# PCB-TLY-SHLD.net
KiCad netlist of a schematic drawn in EAGLE
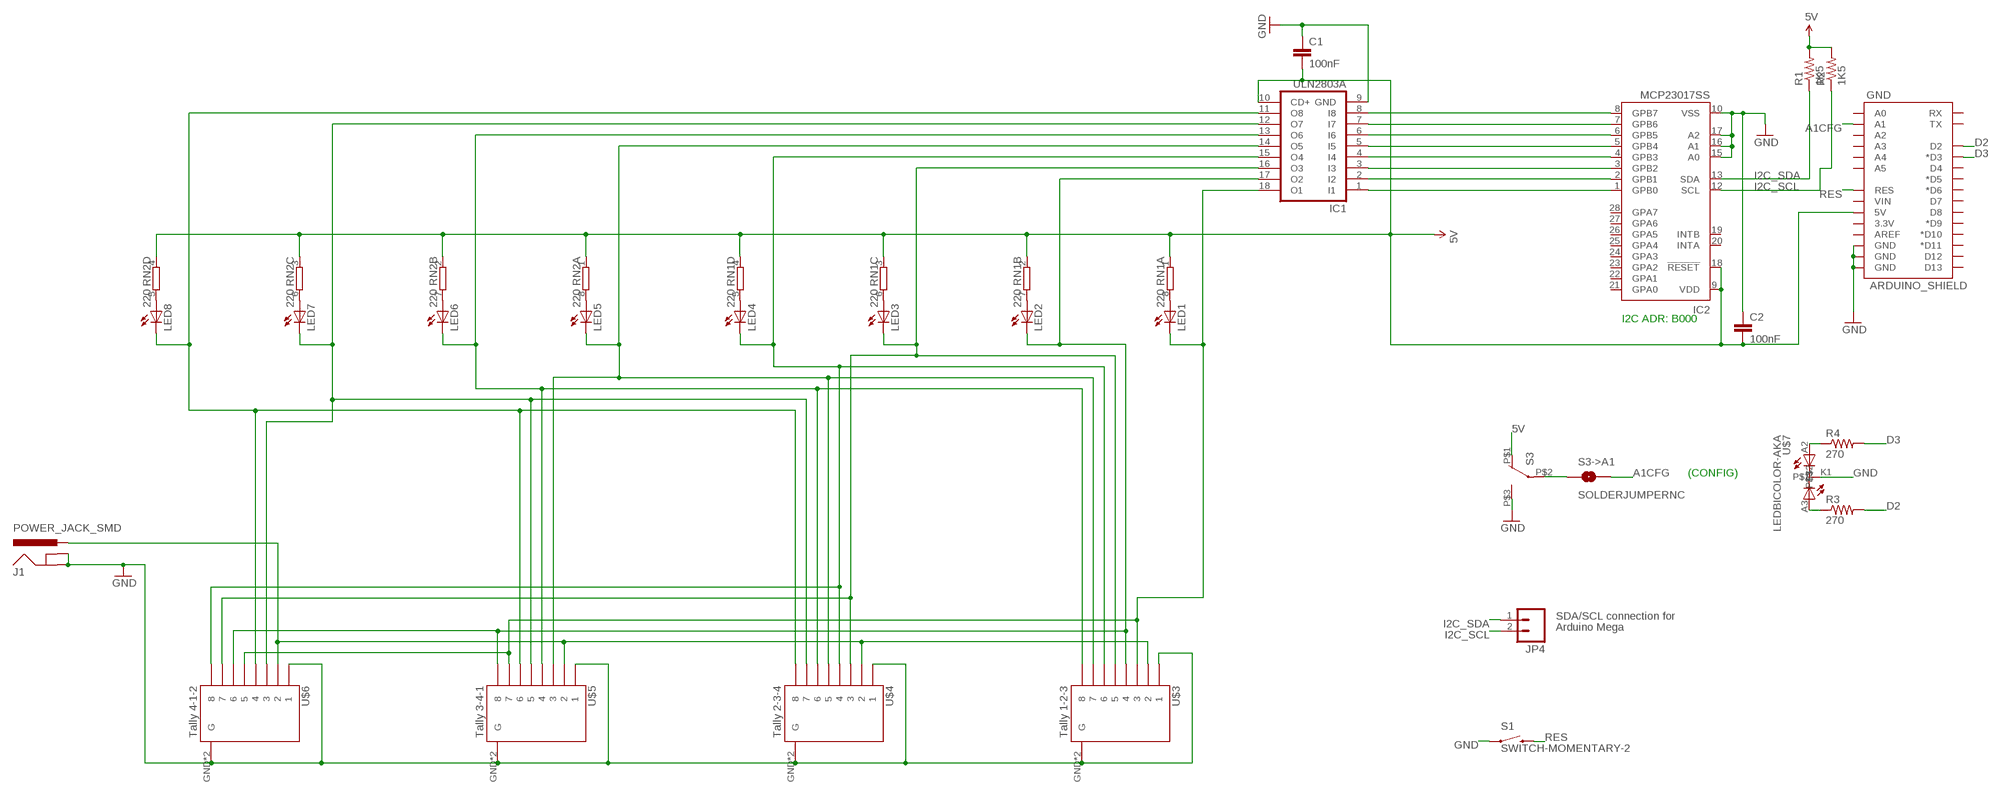
[diagram p0: schematic, sheet 1]

(export (version "E")
  (design (tool "Eeschema 10.0.6"))
  (components
    (comp (ref "C1")
      (value "100nF")
      (footprint "eagle-import:0805")
      (libsource (lib "eagle-import") (part "CAP0805"))
    )
    (comp (ref "C2")
      (value "100nF")
      (footprint "eagle-import:0603-CAP")
      (libsource (lib "eagle-import") (part "CAP0603-CAP"))
    )
    (comp (ref "GND")
      (value "ARDUINO_SHIELD")
      (footprint "eagle-import:ARDUINO_BOXSHIELD_NOHOLES")
      (libsource (lib "eagle-import") (part "ARDUINO_SHIELD"))
    )
    (comp (ref "IC1")
      (value "ULN2803A")
      (footprint "eagle-import:SO18W")
      (libsource (lib "eagle-import") (part "ULN2803ASO18W"))
    )
    (comp (ref "IC2")
      (value "MCP23017SS")
      (footprint "eagle-import:SSOP28")
      (fields (field (name "MF") "MICROCHIP") (field (name "MPN") "MCP23017-E/SS"))
      (libsource (lib "eagle-import") (part "MCP23017SS"))
    )
    (comp (ref "J1")
      (value "POWER_JACK_SMD")
      (footprint "eagle-import:POWER_JACK_SMD")
      (libsource (lib "eagle-import") (part "POWER_JACK_SMD"))
    )
    (comp (ref "JP4")
      (value "M02PTH")
      (footprint "eagle-import:1X02")
      (libsource (lib "eagle-import") (part "M02PTH"))
    )
    (comp (ref "LED1")
      (value "LEDSML0805")
      (footprint "eagle-import:SML0805")
      (libsource (lib "eagle-import") (part "LEDSML0805"))
    )
    (comp (ref "LED2")
      (value "LEDSML0805")
      (footprint "eagle-import:SML0805")
      (libsource (lib "eagle-import") (part "LEDSML0805"))
    )
    (comp (ref "LED3")
      (value "LEDSML0805")
      (footprint "eagle-import:SML0805")
      (libsource (lib "eagle-import") (part "LEDSML0805"))
    )
    (comp (ref "LED4")
      (value "LEDSML0805")
      (footprint "eagle-import:SML0805")
      (libsource (lib "eagle-import") (part "LEDSML0805"))
    )
    (comp (ref "LED5")
      (value "LEDSML0805")
      (footprint "eagle-import:SML0805")
      (libsource (lib "eagle-import") (part "LEDSML0805"))
    )
    (comp (ref "LED6")
      (value "LEDSML0805")
      (footprint "eagle-import:SML0805")
      (libsource (lib "eagle-import") (part "LEDSML0805"))
    )
    (comp (ref "LED7")
      (value "LEDSML0805")
      (footprint "eagle-import:SML0805")
      (libsource (lib "eagle-import") (part "LEDSML0805"))
    )
    (comp (ref "LED8")
      (value "LEDSML0805")
      (footprint "eagle-import:SML0805")
      (libsource (lib "eagle-import") (part "LEDSML0805"))
    )
    (comp (ref "R1")
      (value "1K5")
      (footprint "eagle-import:0603-RES")
      (libsource (lib "eagle-import") (part "RESISTOR0603-RES"))
    )
    (comp (ref "R2")
      (value "1K5")
      (footprint "eagle-import:0603-RES")
      (libsource (lib "eagle-import") (part "RESISTOR0603-RES"))
    )
    (comp (ref "R3")
      (value "270")
      (footprint "eagle-import:0603-RES")
      (libsource (lib "eagle-import") (part "RESISTOR0603-RES"))
    )
    (comp (ref "R4")
      (value "270")
      (footprint "eagle-import:0603-RES")
      (libsource (lib "eagle-import") (part "RESISTOR0603-RES"))
    )
    (comp (ref "RN1")
      (value "220")
      (footprint "eagle-import:CAY16_HAND")
      (libsource (lib "eagle-import") (part "4R-NCAY16"))
    )
    (comp (ref "RN2")
      (value "220")
      (footprint "eagle-import:CAY16_HAND")
      (libsource (lib "eagle-import") (part "4R-NCAY16"))
    )
    (comp (ref "S1")
      (value "SWITCH-MOMENTARY-2")
      (footprint "eagle-import:TACTILE_SWITCH_TALL")
      (libsource (lib "eagle-import") (part "SWITCH-MOMENTARY-2"))
    )
    (comp (ref "S3")
      (value "CFG")
      (footprint "eagle-import:TECONNECTIVITY-DPST")
      (libsource (lib "eagle-import") (part "SWITCH-DPST"))
    )
    (comp (ref "S3->A1")
      (value "SOLDERJUMPERNC")
      (footprint "eagle-import:SJ_2S")
      (libsource (lib "eagle-import") (part "SOLDERJUMPERNC"))
    )
    (comp (ref "U$3")
      (value "Tally 1-2-3")
      (footprint "eagle-import:RJ45-8_GND")
      (libsource (lib "eagle-import") (part "RJ45-8_GND"))
    )
    (comp (ref "U$4")
      (value "Tally 2-3-4")
      (footprint "eagle-import:RJ45-8_GND")
      (libsource (lib "eagle-import") (part "RJ45-8_GND"))
    )
    (comp (ref "U$5")
      (value "Tally 3-4-1")
      (footprint "eagle-import:RJ45-8_GND")
      (libsource (lib "eagle-import") (part "RJ45-8_GND"))
    )
    (comp (ref "U$6")
      (value "Tally 4-1-2")
      (footprint "eagle-import:RJ45-8_GND")
      (libsource (lib "eagle-import") (part "RJ45-8_GND"))
    )
    (comp (ref "U$7")
      (value "LEDBICOLOR-AKA")
      (footprint "eagle-import:LED5MM-BICOLOR")
      (libsource (lib "eagle-import") (part "LEDBICOLOR-AKA"))
    )
  )
  (nets
    (net (code "1") (name "/A1CFG") (class "Default")
      (node (ref "GND") (pin "A1") (pinfunction "A1_A1") (pintype "bidirectional"))
      (node (ref "S3->A1") (pin "2") (pinfunction "2_2") (pintype "passive"))
    )
    (net (code "2") (name "/D2") (class "Default")
      (node (ref "GND") (pin "2") (pinfunction "D2_2") (pintype "bidirectional"))
      (node (ref "R3") (pin "2") (pinfunction "2_2") (pintype "passive"))
    )
    (net (code "3") (name "/D3") (class "Default")
      (node (ref "GND") (pin "3") (pinfunction "*D3_3") (pintype "bidirectional"))
      (node (ref "R4") (pin "2") (pinfunction "2_2") (pintype "passive"))
    )
    (net (code "4") (name "/I2C_SCL") (class "Default")
      (node (ref "IC2") (pin "12") (pinfunction "SCL_12") (pintype "input"))
      (node (ref "JP4") (pin "2") (pinfunction "2_2") (pintype "passive"))
      (node (ref "R2") (pin "1") (pinfunction "1_1") (pintype "passive"))
    )
    (net (code "5") (name "/I2C_SDA") (class "Default")
      (node (ref "IC2") (pin "13") (pinfunction "SDA_13") (pintype "bidirectional"))
      (node (ref "JP4") (pin "1") (pinfunction "1_1") (pintype "passive"))
      (node (ref "R1") (pin "1") (pinfunction "1_1") (pintype "passive"))
    )
    (net (code "6") (name "/RES") (class "Default")
      (node (ref "GND") (pin "RESET") (pinfunction "RES_RESET") (pintype "bidirectional"))
      (node (ref "S1") (pin "B2") (pinfunction "2_B2") (pintype "passive"))
    )
    (net (code "7") (name "5V") (class "Default")
      (node (ref "C1") (pin "2") (pinfunction "2_2") (pintype "passive"))
      (node (ref "C2") (pin "2") (pinfunction "2_2") (pintype "passive"))
      (node (ref "GND") (pin "5V@0") (pinfunction "5V_5V@0") (pintype "bidirectional"))
      (node (ref "IC1") (pin "10") (pinfunction "CD+_10") (pintype "passive"))
      (node (ref "IC2") (pin "18") (pinfunction "~{RESET}_18") (pintype "input"))
      (node (ref "IC2") (pin "9") (pinfunction "VDD_9") (pintype "power_in"))
      (node (ref "R1") (pin "2") (pinfunction "2_2") (pintype "passive"))
      (node (ref "R2") (pin "2") (pinfunction "2_2") (pintype "passive"))
      (node (ref "RN1") (pin "1") (pinfunction "1_1") (pintype "passive"))
      (node (ref "RN1") (pin "2") (pinfunction "1_2") (pintype "passive"))
      (node (ref "RN1") (pin "3") (pinfunction "1_3") (pintype "passive"))
      (node (ref "RN1") (pin "4") (pinfunction "1_4") (pintype "passive"))
      (node (ref "RN2") (pin "1") (pinfunction "1_1") (pintype "passive"))
      (node (ref "RN2") (pin "2") (pinfunction "1_2") (pintype "passive"))
      (node (ref "RN2") (pin "3") (pinfunction "1_3") (pintype "passive"))
      (node (ref "RN2") (pin "4") (pinfunction "1_4") (pintype "passive"))
      (node (ref "S3") (pin "P$1") (pinfunction "O_P$1") (pintype "passive"))
    )
    (net (code "8") (name "GND") (class "Default")
      (node (ref "C1") (pin "1") (pinfunction "1_1") (pintype "passive"))
      (node (ref "C2") (pin "1") (pinfunction "1_1") (pintype "passive"))
      (node (ref "GND") (pin "GND@0") (pinfunction "GND_GND@0") (pintype "bidirectional"))
      (node (ref "GND") (pin "GND@1") (pinfunction "GND_GND@1") (pintype "bidirectional"))
      (node (ref "GND") (pin "GND@4") (pinfunction "GND_GND@4") (pintype "bidirectional"))
      (node (ref "IC1") (pin "9") (pinfunction "GND_9") (pintype "power_in"))
      (node (ref "IC2") (pin "10") (pinfunction "VSS_10") (pintype "power_in"))
      (node (ref "IC2") (pin "15") (pinfunction "A0_15") (pintype "input"))
      (node (ref "IC2") (pin "16") (pinfunction "A1_16") (pintype "input"))
      (node (ref "IC2") (pin "17") (pinfunction "A2_17") (pintype "input"))
      (node (ref "J1") (pin "GND") (pinfunction "GND_GND") (pintype "bidirectional"))
      (node (ref "J1") (pin "SHUNT") (pinfunction "GNDBREAK_SHUNT") (pintype "bidirectional"))
      (node (ref "S1") (pin "A2") (pinfunction "1_A2") (pintype "passive"))
      (node (ref "S3") (pin "P$3") (pinfunction "S_P$3") (pintype "passive"))
      (node (ref "U$3") (pin "1") (pinfunction "1_1") (pintype "bidirectional"))
      (node (ref "U$3") (pin "GND") (pinfunction "G_GND") (pintype "power_in"))
      (node (ref "U$3") (pin "GND1") (pinfunction "G_GND1") (pintype "power_in"))
      (node (ref "U$4") (pin "1") (pinfunction "1_1") (pintype "bidirectional"))
      (node (ref "U$4") (pin "GND") (pinfunction "G_GND") (pintype "power_in"))
      (node (ref "U$4") (pin "GND1") (pinfunction "G_GND1") (pintype "power_in"))
      (node (ref "U$5") (pin "1") (pinfunction "1_1") (pintype "bidirectional"))
      (node (ref "U$5") (pin "GND") (pinfunction "G_GND") (pintype "power_in"))
      (node (ref "U$5") (pin "GND1") (pinfunction "G_GND1") (pintype "power_in"))
      (node (ref "U$6") (pin "1") (pinfunction "1_1") (pintype "bidirectional"))
      (node (ref "U$6") (pin "GND") (pinfunction "G_GND") (pintype "power_in"))
      (node (ref "U$6") (pin "GND1") (pinfunction "G_GND1") (pintype "power_in"))
      (node (ref "U$7") (pin "K1") (pinfunction "P$1_K1") (pintype "bidirectional"))
    )
    (net (code "9") (name "Net-(IC1-I1)") (class "Default")
      (node (ref "IC1") (pin "1") (pinfunction "I1_1") (pintype "input"))
      (node (ref "IC2") (pin "1") (pinfunction "GPB0_1") (pintype "bidirectional"))
    )
    (net (code "10") (name "Net-(IC1-I2)") (class "Default")
      (node (ref "IC1") (pin "2") (pinfunction "I2_2") (pintype "input"))
      (node (ref "IC2") (pin "2") (pinfunction "GPB1_2") (pintype "bidirectional"))
    )
    (net (code "11") (name "Net-(IC1-I3)") (class "Default")
      (node (ref "IC1") (pin "3") (pinfunction "I3_3") (pintype "input"))
      (node (ref "IC2") (pin "3") (pinfunction "GPB2_3") (pintype "bidirectional"))
    )
    (net (code "12") (name "Net-(IC1-I4)") (class "Default")
      (node (ref "IC1") (pin "4") (pinfunction "I4_4") (pintype "input"))
      (node (ref "IC2") (pin "4") (pinfunction "GPB3_4") (pintype "bidirectional"))
    )
    (net (code "13") (name "Net-(IC1-I5)") (class "Default")
      (node (ref "IC1") (pin "5") (pinfunction "I5_5") (pintype "input"))
      (node (ref "IC2") (pin "5") (pinfunction "GPB4_5") (pintype "bidirectional"))
    )
    (net (code "14") (name "Net-(IC1-I6)") (class "Default")
      (node (ref "IC1") (pin "6") (pinfunction "I6_6") (pintype "input"))
      (node (ref "IC2") (pin "6") (pinfunction "GPB5_6") (pintype "bidirectional"))
    )
    (net (code "15") (name "Net-(IC1-I7)") (class "Default")
      (node (ref "IC1") (pin "7") (pinfunction "I7_7") (pintype "input"))
      (node (ref "IC2") (pin "7") (pinfunction "GPB6_7") (pintype "bidirectional"))
    )
    (net (code "16") (name "Net-(IC1-I8)") (class "Default")
      (node (ref "IC1") (pin "8") (pinfunction "I8_8") (pintype "input"))
      (node (ref "IC2") (pin "8") (pinfunction "GPB7_8") (pintype "bidirectional"))
    )
    (net (code "17") (name "Net-(IC1-O1)") (class "Default")
      (node (ref "IC1") (pin "18") (pinfunction "O1_18") (pintype "open_collector"))
      (node (ref "LED1") (pin "C") (pinfunction "C_C") (pintype "passive"))
      (node (ref "U$3") (pin "3") (pinfunction "3_3") (pintype "bidirectional"))
      (node (ref "U$5") (pin "7") (pinfunction "7_7") (pintype "bidirectional"))
      (node (ref "U$6") (pin "5") (pinfunction "5_5") (pintype "bidirectional"))
    )
    (net (code "18") (name "Net-(IC1-O2)") (class "Default")
      (node (ref "IC1") (pin "17") (pinfunction "O2_17") (pintype "open_collector"))
      (node (ref "LED2") (pin "C") (pinfunction "C_C") (pintype "passive"))
      (node (ref "U$3") (pin "4") (pinfunction "4_4") (pintype "bidirectional"))
      (node (ref "U$5") (pin "8") (pinfunction "8_8") (pintype "bidirectional"))
      (node (ref "U$6") (pin "6") (pinfunction "6_6") (pintype "bidirectional"))
    )
    (net (code "19") (name "Net-(IC1-O3)") (class "Default")
      (node (ref "IC1") (pin "16") (pinfunction "O3_16") (pintype "open_collector"))
      (node (ref "LED3") (pin "C") (pinfunction "C_C") (pintype "passive"))
      (node (ref "U$3") (pin "5") (pinfunction "5_5") (pintype "bidirectional"))
      (node (ref "U$4") (pin "3") (pinfunction "3_3") (pintype "bidirectional"))
      (node (ref "U$6") (pin "7") (pinfunction "7_7") (pintype "bidirectional"))
    )
    (net (code "20") (name "Net-(IC1-O4)") (class "Default")
      (node (ref "IC1") (pin "15") (pinfunction "O4_15") (pintype "open_collector"))
      (node (ref "LED4") (pin "C") (pinfunction "C_C") (pintype "passive"))
      (node (ref "U$3") (pin "6") (pinfunction "6_6") (pintype "bidirectional"))
      (node (ref "U$4") (pin "4") (pinfunction "4_4") (pintype "bidirectional"))
      (node (ref "U$6") (pin "8") (pinfunction "8_8") (pintype "bidirectional"))
    )
    (net (code "21") (name "Net-(IC1-O5)") (class "Default")
      (node (ref "IC1") (pin "14") (pinfunction "O5_14") (pintype "open_collector"))
      (node (ref "LED5") (pin "C") (pinfunction "C_C") (pintype "passive"))
      (node (ref "U$3") (pin "7") (pinfunction "7_7") (pintype "bidirectional"))
      (node (ref "U$4") (pin "5") (pinfunction "5_5") (pintype "bidirectional"))
      (node (ref "U$5") (pin "3") (pinfunction "3_3") (pintype "bidirectional"))
    )
    (net (code "22") (name "Net-(IC1-O6)") (class "Default")
      (node (ref "IC1") (pin "13") (pinfunction "O6_13") (pintype "open_collector"))
      (node (ref "LED6") (pin "C") (pinfunction "C_C") (pintype "passive"))
      (node (ref "U$3") (pin "8") (pinfunction "8_8") (pintype "bidirectional"))
      (node (ref "U$4") (pin "6") (pinfunction "6_6") (pintype "bidirectional"))
      (node (ref "U$5") (pin "4") (pinfunction "4_4") (pintype "bidirectional"))
    )
    (net (code "23") (name "Net-(IC1-O7)") (class "Default")
      (node (ref "IC1") (pin "12") (pinfunction "O7_12") (pintype "open_collector"))
      (node (ref "LED7") (pin "C") (pinfunction "C_C") (pintype "passive"))
      (node (ref "U$4") (pin "7") (pinfunction "7_7") (pintype "bidirectional"))
      (node (ref "U$5") (pin "5") (pinfunction "5_5") (pintype "bidirectional"))
      (node (ref "U$6") (pin "3") (pinfunction "3_3") (pintype "bidirectional"))
    )
    (net (code "24") (name "Net-(IC1-O8)") (class "Default")
      (node (ref "IC1") (pin "11") (pinfunction "O8_11") (pintype "open_collector"))
      (node (ref "LED8") (pin "C") (pinfunction "C_C") (pintype "passive"))
      (node (ref "U$4") (pin "8") (pinfunction "8_8") (pintype "bidirectional"))
      (node (ref "U$5") (pin "6") (pinfunction "6_6") (pintype "bidirectional"))
      (node (ref "U$6") (pin "4") (pinfunction "4_4") (pintype "bidirectional"))
    )
    (net (code "25") (name "Net-(J1-PadPWR)") (class "Default")
      (node (ref "J1") (pin "PWR") (pinfunction "PWR_PWR") (pintype "bidirectional"))
      (node (ref "U$3") (pin "2") (pinfunction "2_2") (pintype "bidirectional"))
      (node (ref "U$4") (pin "2") (pinfunction "2_2") (pintype "bidirectional"))
      (node (ref "U$5") (pin "2") (pinfunction "2_2") (pintype "bidirectional"))
      (node (ref "U$6") (pin "2") (pinfunction "2_2") (pintype "bidirectional"))
    )
    (net (code "26") (name "Net-(RN1A-2)") (class "Default")
      (node (ref "LED1") (pin "A") (pinfunction "A_A") (pintype "passive"))
      (node (ref "RN1") (pin "8") (pinfunction "2_8") (pintype "passive"))
    )
    (net (code "27") (name "Net-(RN1B-2)") (class "Default")
      (node (ref "LED2") (pin "A") (pinfunction "A_A") (pintype "passive"))
      (node (ref "RN1") (pin "7") (pinfunction "2_7") (pintype "passive"))
    )
    (net (code "28") (name "Net-(RN1C-2)") (class "Default")
      (node (ref "LED3") (pin "A") (pinfunction "A_A") (pintype "passive"))
      (node (ref "RN1") (pin "6") (pinfunction "2_6") (pintype "passive"))
    )
    (net (code "29") (name "Net-(RN1D-2)") (class "Default")
      (node (ref "LED4") (pin "A") (pinfunction "A_A") (pintype "passive"))
      (node (ref "RN1") (pin "5") (pinfunction "2_5") (pintype "passive"))
    )
    (net (code "30") (name "Net-(RN2A-2)") (class "Default")
      (node (ref "LED5") (pin "A") (pinfunction "A_A") (pintype "passive"))
      (node (ref "RN2") (pin "8") (pinfunction "2_8") (pintype "passive"))
    )
    (net (code "31") (name "Net-(RN2B-2)") (class "Default")
      (node (ref "LED6") (pin "A") (pinfunction "A_A") (pintype "passive"))
      (node (ref "RN2") (pin "7") (pinfunction "2_7") (pintype "passive"))
    )
    (net (code "32") (name "Net-(RN2C-2)") (class "Default")
      (node (ref "LED7") (pin "A") (pinfunction "A_A") (pintype "passive"))
      (node (ref "RN2") (pin "6") (pinfunction "2_6") (pintype "passive"))
    )
    (net (code "33") (name "Net-(RN2D-2)") (class "Default")
      (node (ref "LED8") (pin "A") (pinfunction "A_A") (pintype "passive"))
      (node (ref "RN2") (pin "5") (pinfunction "2_5") (pintype "passive"))
    )
    (net (code "34") (name "Net-(S3-P)") (class "Default")
      (node (ref "S3") (pin "P$2") (pinfunction "P_P$2") (pintype "passive"))
      (node (ref "S3->A1") (pin "1") (pinfunction "1_1") (pintype "passive"))
    )
    (net (code "35") (name "Net-(U$7-P$2)") (class "Default")
      (node (ref "R4") (pin "1") (pinfunction "1_1") (pintype "passive"))
      (node (ref "U$7") (pin "A2") (pinfunction "P$2_A2") (pintype "bidirectional"))
    )
    (net (code "36") (name "Net-(U$7-P$3)") (class "Default")
      (node (ref "R3") (pin "1") (pinfunction "1_1") (pintype "passive"))
      (node (ref "U$7") (pin "A3") (pinfunction "P$3_A3") (pintype "bidirectional"))
    )
    (net (code "37") (name "unconnected-(GND-*D5-Pad5)") (class "Default")
      (node (ref "GND") (pin "5") (pinfunction "*D5_5") (pintype "bidirectional"))
    )
    (net (code "38") (name "unconnected-(GND-*D6-Pad6)") (class "Default")
      (node (ref "GND") (pin "6") (pinfunction "*D6_6") (pintype "bidirectional"))
    )
    (net (code "39") (name "unconnected-(GND-*D9-Pad9)") (class "Default")
      (node (ref "GND") (pin "9") (pinfunction "*D9_9") (pintype "bidirectional"))
    )
    (net (code "40") (name "unconnected-(GND-*D10-Pad10)") (class "Default")
      (node (ref "GND") (pin "10") (pinfunction "*D10_10") (pintype "bidirectional"))
    )
    (net (code "41") (name "unconnected-(GND-*D11-Pad11)") (class "Default")
      (node (ref "GND") (pin "11") (pinfunction "*D11_11") (pintype "bidirectional"))
    )
    (net (code "42") (name "unconnected-(GND-D4-Pad4)") (class "Default")
      (node (ref "GND") (pin "4") (pinfunction "D4_4") (pintype "bidirectional"))
    )
    (net (code "43") (name "unconnected-(GND-D7-Pad7)") (class "Default")
      (node (ref "GND") (pin "7") (pinfunction "D7_7") (pintype "bidirectional"))
    )
    (net (code "44") (name "unconnected-(GND-D8-Pad8)") (class "Default")
      (node (ref "GND") (pin "8") (pinfunction "D8_8") (pintype "bidirectional"))
    )
    (net (code "45") (name "unconnected-(GND-D12-Pad12)") (class "Default")
      (node (ref "GND") (pin "12") (pinfunction "D12_12") (pintype "bidirectional"))
    )
    (net (code "46") (name "unconnected-(GND-D13-Pad13)") (class "Default")
      (node (ref "GND") (pin "13") (pinfunction "D13_13") (pintype "bidirectional"))
    )
    (net (code "47") (name "unconnected-(GND-Pad3.3V)") (class "Default")
      (node (ref "GND") (pin "3.3V") (pinfunction "3.3V_3.3V") (pintype "bidirectional"))
    )
    (net (code "48") (name "unconnected-(GND-PadA0)") (class "Default")
      (node (ref "GND") (pin "A0") (pinfunction "A0_A0") (pintype "bidirectional"))
    )
    (net (code "49") (name "unconnected-(GND-PadA2)") (class "Default")
      (node (ref "GND") (pin "A2") (pinfunction "A2_A2") (pintype "bidirectional"))
    )
    (net (code "50") (name "unconnected-(GND-PadA3)") (class "Default")
      (node (ref "GND") (pin "A3") (pinfunction "A3_A3") (pintype "bidirectional"))
    )
    (net (code "51") (name "unconnected-(GND-PadA4)") (class "Default")
      (node (ref "GND") (pin "A4") (pinfunction "A4_A4") (pintype "bidirectional"))
    )
    (net (code "52") (name "unconnected-(GND-PadA5)") (class "Default")
      (node (ref "GND") (pin "A5") (pinfunction "A5_A5") (pintype "bidirectional"))
    )
    (net (code "53") (name "unconnected-(GND-PadAREF)") (class "Default")
      (node (ref "GND") (pin "AREF") (pinfunction "AREF_AREF") (pintype "bidirectional"))
    )
    (net (code "54") (name "unconnected-(GND-PadVIN)") (class "Default")
      (node (ref "GND") (pin "VIN") (pinfunction "VIN_VIN") (pintype "bidirectional"))
    )
    (net (code "55") (name "unconnected-(GND-RX-Pad0)") (class "Default")
      (node (ref "GND") (pin "0") (pinfunction "RX_0") (pintype "bidirectional"))
    )
    (net (code "56") (name "unconnected-(GND-TX-Pad1)") (class "Default")
      (node (ref "GND") (pin "1") (pinfunction "TX_1") (pintype "bidirectional"))
    )
    (net (code "57") (name "unconnected-(IC2-GPA0-Pad21)") (class "Default")
      (node (ref "IC2") (pin "21") (pinfunction "GPA0_21") (pintype "bidirectional"))
    )
    (net (code "58") (name "unconnected-(IC2-GPA1-Pad22)") (class "Default")
      (node (ref "IC2") (pin "22") (pinfunction "GPA1_22") (pintype "bidirectional"))
    )
    (net (code "59") (name "unconnected-(IC2-GPA2-Pad23)") (class "Default")
      (node (ref "IC2") (pin "23") (pinfunction "GPA2_23") (pintype "bidirectional"))
    )
    (net (code "60") (name "unconnected-(IC2-GPA3-Pad24)") (class "Default")
      (node (ref "IC2") (pin "24") (pinfunction "GPA3_24") (pintype "bidirectional"))
    )
    (net (code "61") (name "unconnected-(IC2-GPA4-Pad25)") (class "Default")
      (node (ref "IC2") (pin "25") (pinfunction "GPA4_25") (pintype "bidirectional"))
    )
    (net (code "62") (name "unconnected-(IC2-GPA5-Pad26)") (class "Default")
      (node (ref "IC2") (pin "26") (pinfunction "GPA5_26") (pintype "bidirectional"))
    )
    (net (code "63") (name "unconnected-(IC2-GPA6-Pad27)") (class "Default")
      (node (ref "IC2") (pin "27") (pinfunction "GPA6_27") (pintype "bidirectional"))
    )
    (net (code "64") (name "unconnected-(IC2-GPA7-Pad28)") (class "Default")
      (node (ref "IC2") (pin "28") (pinfunction "GPA7_28") (pintype "bidirectional"))
    )
    (net (code "65") (name "unconnected-(IC2-INTA-Pad20)") (class "Default")
      (node (ref "IC2") (pin "20") (pinfunction "INTA_20") (pintype "output"))
    )
    (net (code "66") (name "unconnected-(IC2-INTB-Pad19)") (class "Default")
      (node (ref "IC2") (pin "19") (pinfunction "INTB_19") (pintype "output"))
    )
  )
)
